# Sheet1.net
KiCad netlist of a schematic drawn in Altium Designer
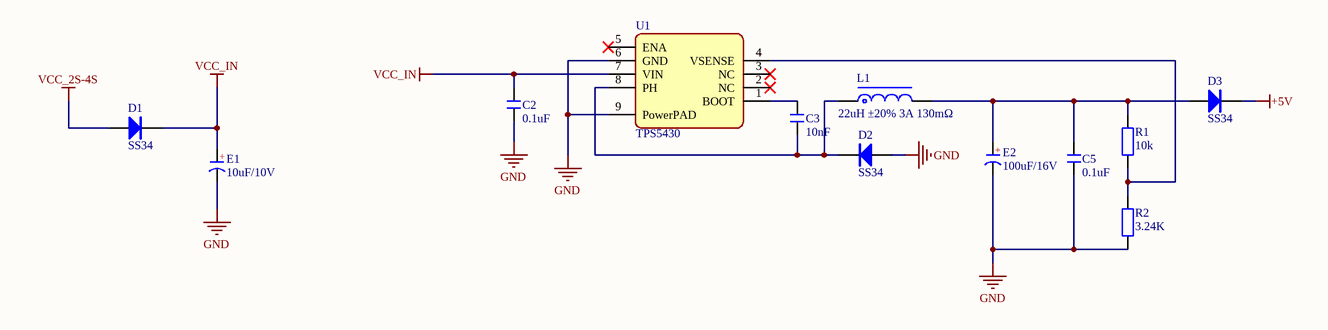
[diagram p0: Sheet1.SchDoc]

(export (version "E")
  (design (tool "Eeschema 10.0.6"))
  (components
    (comp (ref "C2")
      (value "0.1uF")
      (footprint "C 0805_L")
      (description "无极性贴片电容")
      (fields (field (name "版权归属") "源创客"))
      (libsource (lib "Z-LibAll") (part "C"))
    )
    (comp (ref "C3")
      (value "10nF")
      (footprint "C 0805_L")
      (description "无极性贴片电容")
      (fields (field (name "版权归属") "源创客"))
      (libsource (lib "Z-LibAll") (part "C"))
    )
    (comp (ref "C5")
      (value "0.1uF")
      (footprint "C 0805_L")
      (description "无极性贴片电容")
      (fields (field (name "版权归属") "源创客"))
      (libsource (lib "Z-LibAll") (part "C"))
    )
    (comp (ref "D1")
      (value "SS34")
      (footprint "SMC")
      (description "肖特基二极管")
      (fields (field (name "版权归属") "源创客"))
      (libsource (lib "Z-LibAll") (part "SS34"))
    )
    (comp (ref "D2")
      (value "SS34")
      (footprint "SMC")
      (description "肖特基二极管")
      (fields (field (name "版权归属") "源创客"))
      (libsource (lib "Z-LibAll") (part "SS34"))
    )
    (comp (ref "D3")
      (value "SS34")
      (footprint "SMC")
      (description "肖特基二极管")
      (fields (field (name "版权归属") "源创客"))
      (libsource (lib "Z-LibAll") (part "SS34"))
    )
    (comp (ref "E1")
      (value "10uF/10V")
      (footprint "CT 10*8 - R")
      (description "贴片固态电容")
      (fields (field (name "版权归属") "源创客"))
      (libsource (lib "电容") (part "C-CT"))
    )
    (comp (ref "E2")
      (value "100uF/16V")
      (footprint "CD B(3528)")
      (description "贴片钽电容")
      (fields (field (name "版权归属") "源创客"))
      (libsource (lib "Z-LibAll") (part "C-CD"))
    )
    (comp (ref "L1")
      (value "22uH ±20% 3A 130mΩ")
      (footprint "22uH ±20% 3A 130mΩ")
      (description "贴片功率电感")
      (fields (field (name "版权归属") "源创客"))
      (libsource (lib "电感") (part "L-CD"))
    )
    (comp (ref "R1")
      (value "10k")
      (footprint "R 0805_L")
      (description "贴片电阻")
      (fields (field (name "版权归属") "源创客"))
      (libsource (lib "Z-LibAll") (part "R"))
    )
    (comp (ref "R2")
      (value "3.24K")
      (footprint "R 0805_L")
      (description "贴片电阻")
      (fields (field (name "版权归属") "源创客"))
      (libsource (lib "Z-LibAll") (part "R"))
    )
    (comp (ref "U1")
      (value "TPS5430")
      (footprint "TPS5430")
      (description "LC_C9864")
      (libsource (lib "Z-LibAll") (part "TPS5430"))
    )
  )
  (nets
    (net (code "1") (name "+5V") (class "Default")
      (node (ref "D3") (pin "2") (pinfunction "K_2") (pintype "passive"))
    )
    (net (code "2") (name "GND") (class "Default")
      (node (ref "C2") (pin "1") (pinfunction "1_1") (pintype "passive"))
      (node (ref "C5") (pin "1") (pinfunction "1_1") (pintype "passive"))
      (node (ref "D2") (pin "1") (pinfunction "A_1") (pintype "passive"))
      (node (ref "E1") (pin "2") (pinfunction "K_2") (pintype "passive"))
      (node (ref "E2") (pin "2") (pinfunction "K_2") (pintype "passive"))
      (node (ref "R2") (pin "1") (pinfunction "1_1") (pintype "passive"))
      (node (ref "U1") (pin "6") (pinfunction "GND_6") (pintype "passive"))
      (node (ref "U1") (pin "9") (pinfunction "PowerPAD_9") (pintype "passive"))
    )
    (net (code "3") (name "Net-(D2-K)") (class "Default")
      (node (ref "C3") (pin "1") (pinfunction "1_1") (pintype "passive"))
      (node (ref "D2") (pin "2") (pinfunction "K_2") (pintype "passive"))
      (node (ref "L1") (pin "1") (pinfunction "1_1") (pintype "passive"))
      (node (ref "U1") (pin "8") (pinfunction "PH_8") (pintype "passive"))
    )
    (net (code "4") (name "Net-(D3-A)") (class "Default")
      (node (ref "C5") (pin "2") (pinfunction "2_2") (pintype "passive"))
      (node (ref "D3") (pin "1") (pinfunction "A_1") (pintype "passive"))
      (node (ref "E2") (pin "1") (pinfunction "A_1") (pintype "passive"))
      (node (ref "L1") (pin "2") (pinfunction "2_2") (pintype "passive"))
      (node (ref "R1") (pin "2") (pinfunction "2_2") (pintype "passive"))
    )
    (net (code "5") (name "Net-(U1-BOOT)") (class "Default")
      (node (ref "C3") (pin "2") (pinfunction "2_2") (pintype "passive"))
      (node (ref "U1") (pin "1") (pinfunction "BOOT_1") (pintype "passive"))
    )
    (net (code "6") (name "Net-(U1-VSENSE)") (class "Default")
      (node (ref "R1") (pin "1") (pinfunction "1_1") (pintype "passive"))
      (node (ref "R2") (pin "2") (pinfunction "2_2") (pintype "passive"))
      (node (ref "U1") (pin "4") (pinfunction "VSENSE_4") (pintype "passive"))
    )
    (net (code "7") (name "VCC_2S-4S") (class "Default")
      (node (ref "D1") (pin "1") (pinfunction "A_1") (pintype "passive"))
    )
    (net (code "8") (name "VCC_IN") (class "Default")
      (node (ref "C2") (pin "2") (pinfunction "2_2") (pintype "passive"))
      (node (ref "D1") (pin "2") (pinfunction "K_2") (pintype "passive"))
      (node (ref "E1") (pin "1") (pinfunction "A_1") (pintype "passive"))
      (node (ref "U1") (pin "7") (pinfunction "VIN_7") (pintype "passive"))
    )
    (net (code "9") (name "unconnected-(U1-ENA-Pad5)") (class "Default")
      (node (ref "U1") (pin "5") (pinfunction "ENA_5") (pintype "passive+no_connect"))
    )
    (net (code "10") (name "unconnected-(U1-NC-Pad2)") (class "Default")
      (node (ref "U1") (pin "2") (pinfunction "NC_2") (pintype "passive+no_connect"))
    )
    (net (code "11") (name "unconnected-(U1-NC-Pad3)") (class "Default")
      (node (ref "U1") (pin "3") (pinfunction "NC_3") (pintype "passive+no_connect"))
    )
  )
)
